# Right.net
KiCad netlist of a schematic drawn in EAGLE
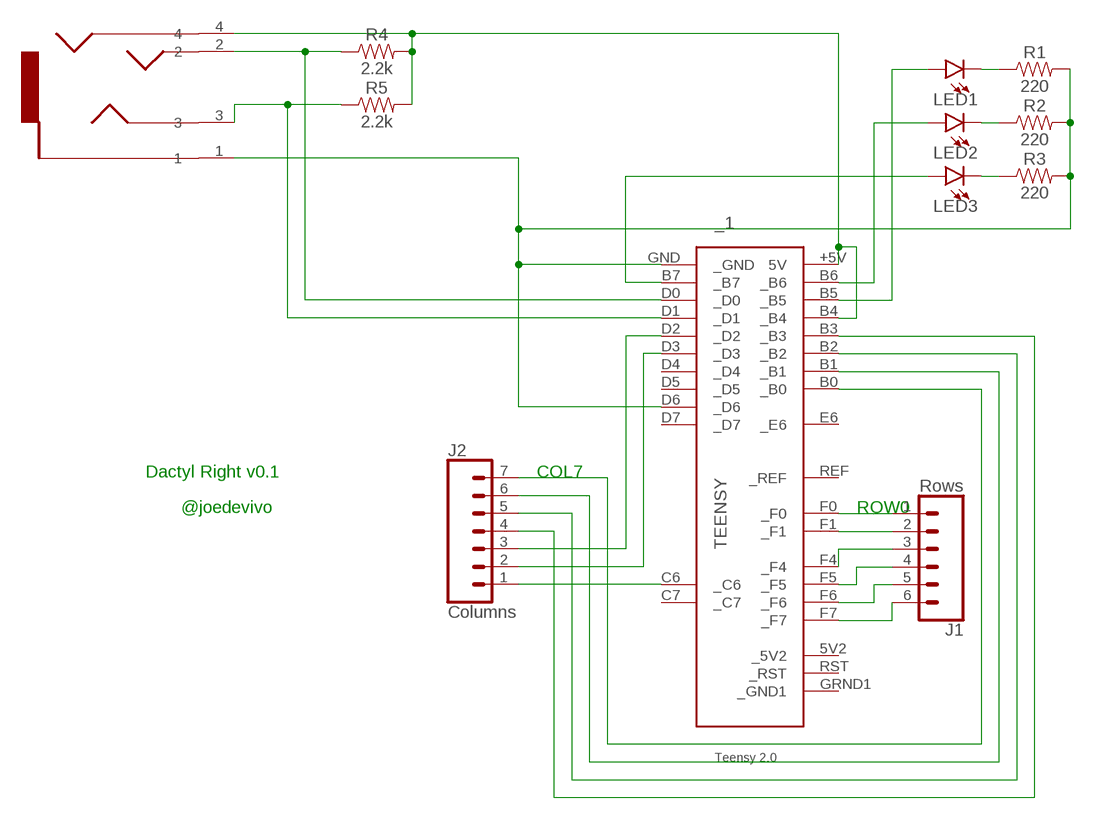
[diagram p0: schematic, sheet 1]

(export (version "E")
  (design (tool "Eeschema 10.0.6"))
  (components
    (comp (ref "J1")
      (value "Rows")
      (footprint "eagle-import:1X06")
      (libsource (lib "eagle-import") (part "CONN_06SILK_FEMALE_PTH"))
    )
    (comp (ref "J2")
      (value "Columns")
      (footprint "eagle-import:1X07")
      (libsource (lib "eagle-import") (part "CONN_07"))
    )
    (comp (ref "LED1")
      (value "LED3MM")
      (footprint "eagle-import:LED_3MM")
      (libsource (lib "eagle-import") (part "LED3MM"))
    )
    (comp (ref "LED2")
      (value "LED3MM")
      (footprint "eagle-import:LED_3MM")
      (libsource (lib "eagle-import") (part "LED3MM"))
    )
    (comp (ref "LED3")
      (value "LED3MM")
      (footprint "eagle-import:LED_3MM")
      (libsource (lib "eagle-import") (part "LED3MM"))
    )
    (comp (ref "R1")
      (value "220")
      (footprint "eagle-import:AXIAL-0.3")
      (libsource (lib "eagle-import") (part "RESISTORAXIAL-0.3"))
    )
    (comp (ref "R2")
      (value "220")
      (footprint "eagle-import:AXIAL-0.3")
      (libsource (lib "eagle-import") (part "RESISTORAXIAL-0.3"))
    )
    (comp (ref "R3")
      (value "220")
      (footprint "eagle-import:AXIAL-0.3")
      (libsource (lib "eagle-import") (part "RESISTORAXIAL-0.3"))
    )
    (comp (ref "R4")
      (value "2.2k")
      (footprint "eagle-import:AXIAL-0.3")
      (libsource (lib "eagle-import") (part "RESISTORAXIAL-0.3"))
    )
    (comp (ref "R5")
      (value "2.2k")
      (footprint "eagle-import:AXIAL-0.3")
      (libsource (lib "eagle-import") (part "RESISTORAXIAL-0.3"))
    )
    (comp (ref "U$2")
      (value "SJ-43514_HEADPHONES_3.5MM_X4")
      (footprint "eagle-import:SJ-43514_HEADPHONES-3.5MM_X4")
      (libsource (lib "eagle-import") (part "SJ-43514_HEADPHONES_3.5MM_X4"))
    )
    (comp (ref "_1")
      (value "TEENSY")
      (footprint "eagle-import:TEENSY")
      (libsource (lib "eagle-import") (part "TEENSY"))
    )
  )
  (nets
    (net (code "1") (name "/COL7") (class "Default")
      (node (ref "J2") (pin "7") (pinfunction "7_7") (pintype "passive"))
      (node (ref "_1") (pin "B0") (pinfunction "_B0_B0") (pintype "bidirectional"))
    )
    (net (code "2") (name "/ROW0") (class "Default")
      (node (ref "J1") (pin "1") (pinfunction "1_1") (pintype "passive"))
      (node (ref "_1") (pin "F0") (pinfunction "_F0_F0") (pintype "bidirectional"))
    )
    (net (code "3") (name "Net-(LED1-C)") (class "Default")
      (node (ref "LED1") (pin "K") (pinfunction "C_K") (pintype "passive"))
      (node (ref "R1") (pin "P$1") (pinfunction "1_P$1") (pintype "passive"))
    )
    (net (code "4") (name "Net-(LED2-C)") (class "Default")
      (node (ref "LED2") (pin "K") (pinfunction "C_K") (pintype "passive"))
      (node (ref "R2") (pin "P$1") (pinfunction "1_P$1") (pintype "passive"))
    )
    (net (code "5") (name "Net-(LED3-C)") (class "Default")
      (node (ref "LED3") (pin "K") (pinfunction "C_K") (pintype "passive"))
      (node (ref "R3") (pin "P$1") (pinfunction "1_P$1") (pintype "passive"))
    )
    (net (code "6") (name "Net-(R1-2)") (class "Default")
      (node (ref "R1") (pin "P$2") (pinfunction "2_P$2") (pintype "passive"))
      (node (ref "R2") (pin "P$2") (pinfunction "2_P$2") (pintype "passive"))
      (node (ref "R3") (pin "P$2") (pinfunction "2_P$2") (pintype "passive"))
      (node (ref "U$2") (pin "1") (pinfunction "1_1") (pintype "bidirectional"))
      (node (ref "_1") (pin "D6") (pinfunction "_D6_D6") (pintype "bidirectional"))
      (node (ref "_1") (pin "GND") (pinfunction "_GND_GND") (pintype "bidirectional"))
    )
    (net (code "7") (name "Net-(R4-1)") (class "Default")
      (node (ref "R4") (pin "P$1") (pinfunction "1_P$1") (pintype "passive"))
      (node (ref "U$2") (pin "2") (pinfunction "2_2") (pintype "bidirectional"))
      (node (ref "_1") (pin "D0") (pinfunction "_D0_D0") (pintype "bidirectional"))
    )
    (net (code "8") (name "Net-(R4-2)") (class "Default")
      (node (ref "R4") (pin "P$2") (pinfunction "2_P$2") (pintype "passive"))
      (node (ref "R5") (pin "P$2") (pinfunction "2_P$2") (pintype "passive"))
      (node (ref "U$2") (pin "4") (pinfunction "4_4") (pintype "bidirectional"))
      (node (ref "_1") (pin "+5V") (pinfunction "5V_+5V") (pintype "bidirectional"))
      (node (ref "_1") (pin "B4") (pinfunction "_B4_B4") (pintype "bidirectional"))
    )
    (net (code "9") (name "Net-(R5-1)") (class "Default")
      (node (ref "R5") (pin "P$1") (pinfunction "1_P$1") (pintype "passive"))
      (node (ref "U$2") (pin "3") (pinfunction "3_3") (pintype "bidirectional"))
      (node (ref "_1") (pin "D1") (pinfunction "_D1_D1") (pintype "bidirectional"))
    )
    (net (code "10") (name "Net-(_1-_B1)") (class "Default")
      (node (ref "J2") (pin "6") (pinfunction "6_6") (pintype "passive"))
      (node (ref "_1") (pin "B1") (pinfunction "_B1_B1") (pintype "bidirectional"))
    )
    (net (code "11") (name "Net-(_1-_B2)") (class "Default")
      (node (ref "J2") (pin "5") (pinfunction "5_5") (pintype "passive"))
      (node (ref "_1") (pin "B2") (pinfunction "_B2_B2") (pintype "bidirectional"))
    )
    (net (code "12") (name "Net-(_1-_B3)") (class "Default")
      (node (ref "J2") (pin "4") (pinfunction "4_4") (pintype "passive"))
      (node (ref "_1") (pin "B3") (pinfunction "_B3_B3") (pintype "bidirectional"))
    )
    (net (code "13") (name "Net-(_1-_B5)") (class "Default")
      (node (ref "LED1") (pin "A") (pinfunction "A_A") (pintype "passive"))
      (node (ref "_1") (pin "B5") (pinfunction "_B5_B5") (pintype "bidirectional"))
    )
    (net (code "14") (name "Net-(_1-_B6)") (class "Default")
      (node (ref "LED2") (pin "A") (pinfunction "A_A") (pintype "passive"))
      (node (ref "_1") (pin "B6") (pinfunction "_B6_B6") (pintype "bidirectional"))
    )
    (net (code "15") (name "Net-(_1-_B7)") (class "Default")
      (node (ref "LED3") (pin "A") (pinfunction "A_A") (pintype "passive"))
      (node (ref "_1") (pin "B7") (pinfunction "_B7_B7") (pintype "bidirectional"))
    )
    (net (code "16") (name "Net-(_1-_C6)") (class "Default")
      (node (ref "J2") (pin "1") (pinfunction "1_1") (pintype "passive"))
      (node (ref "_1") (pin "C6") (pinfunction "_C6_C6") (pintype "bidirectional"))
    )
    (net (code "17") (name "Net-(_1-_D2)") (class "Default")
      (node (ref "J2") (pin "3") (pinfunction "3_3") (pintype "passive"))
      (node (ref "_1") (pin "D2") (pinfunction "_D2_D2") (pintype "bidirectional"))
    )
    (net (code "18") (name "Net-(_1-_D3)") (class "Default")
      (node (ref "J2") (pin "2") (pinfunction "2_2") (pintype "passive"))
      (node (ref "_1") (pin "D3") (pinfunction "_D3_D3") (pintype "bidirectional"))
    )
    (net (code "19") (name "Net-(_1-_F1)") (class "Default")
      (node (ref "J1") (pin "2") (pinfunction "2_2") (pintype "passive"))
      (node (ref "_1") (pin "F1") (pinfunction "_F1_F1") (pintype "bidirectional"))
    )
    (net (code "20") (name "Net-(_1-_F4)") (class "Default")
      (node (ref "J1") (pin "3") (pinfunction "3_3") (pintype "passive"))
      (node (ref "_1") (pin "F4") (pinfunction "_F4_F4") (pintype "bidirectional"))
    )
    (net (code "21") (name "Net-(_1-_F5)") (class "Default")
      (node (ref "J1") (pin "4") (pinfunction "4_4") (pintype "passive"))
      (node (ref "_1") (pin "F5") (pinfunction "_F5_F5") (pintype "bidirectional"))
    )
    (net (code "22") (name "Net-(_1-_F6)") (class "Default")
      (node (ref "J1") (pin "5") (pinfunction "5_5") (pintype "passive"))
      (node (ref "_1") (pin "F6") (pinfunction "_F6_F6") (pintype "bidirectional"))
    )
    (net (code "23") (name "Net-(_1-_F7)") (class "Default")
      (node (ref "J1") (pin "6") (pinfunction "6_6") (pintype "passive"))
      (node (ref "_1") (pin "F7") (pinfunction "_F7_F7") (pintype "bidirectional"))
    )
    (net (code "24") (name "unconnected-(_1-_5V2-Pad5V2)") (class "Default")
      (node (ref "_1") (pin "5V2") (pinfunction "_5V2_5V2") (pintype "bidirectional"))
    )
    (net (code "25") (name "unconnected-(_1-_C7-PadC7)") (class "Default")
      (node (ref "_1") (pin "C7") (pinfunction "_C7_C7") (pintype "bidirectional"))
    )
    (net (code "26") (name "unconnected-(_1-_D4-PadD4)") (class "Default")
      (node (ref "_1") (pin "D4") (pinfunction "_D4_D4") (pintype "bidirectional"))
    )
    (net (code "27") (name "unconnected-(_1-_D5-PadD5)") (class "Default")
      (node (ref "_1") (pin "D5") (pinfunction "_D5_D5") (pintype "bidirectional"))
    )
    (net (code "28") (name "unconnected-(_1-_D7-PadD7)") (class "Default")
      (node (ref "_1") (pin "D7") (pinfunction "_D7_D7") (pintype "bidirectional"))
    )
    (net (code "29") (name "unconnected-(_1-_E6-PadE6)") (class "Default")
      (node (ref "_1") (pin "E6") (pinfunction "_E6_E6") (pintype "bidirectional"))
    )
    (net (code "30") (name "unconnected-(_1-_GND1-PadGRND1)") (class "Default")
      (node (ref "_1") (pin "GRND1") (pinfunction "_GND1_GRND1") (pintype "bidirectional"))
    )
    (net (code "31") (name "unconnected-(_1-_REF-PadREF)") (class "Default")
      (node (ref "_1") (pin "REF") (pinfunction "_REF_REF") (pintype "bidirectional"))
    )
    (net (code "32") (name "unconnected-(_1-_RST-PadRST)") (class "Default")
      (node (ref "_1") (pin "RST") (pinfunction "_RST_RST") (pintype "bidirectional"))
    )
  )
)
